# SHDN-S07-V00-PSU.net
KiCad netlist of a schematic drawn in Altium Designer
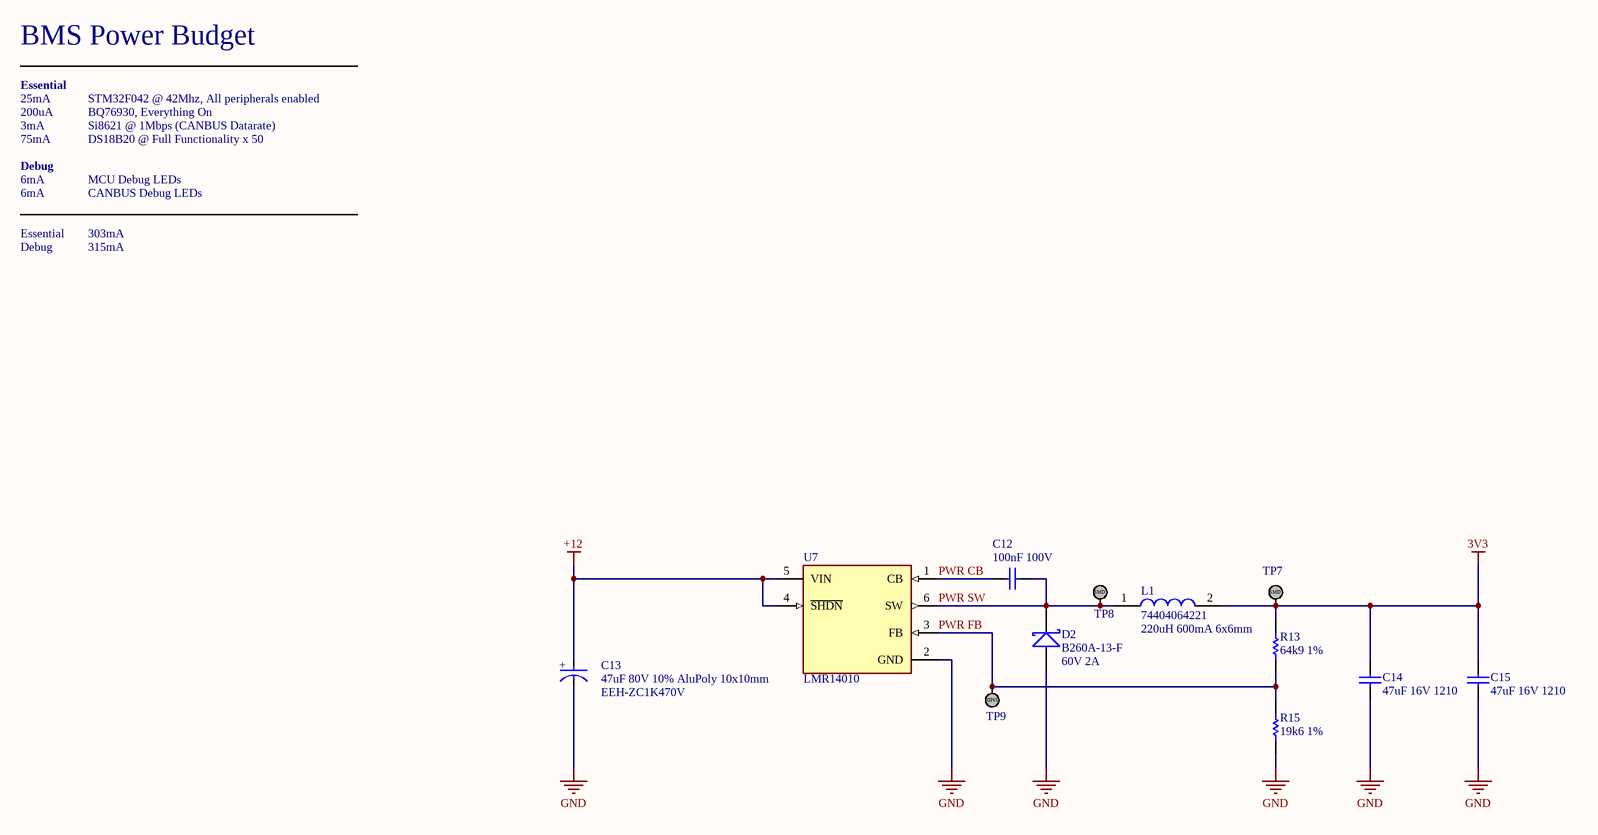
[diagram p0: SHDN-S07-V00-PSU.SchDoc]

(export (version "E")
  (design (tool "Eeschema 10.0.6"))
  (components
    (comp (ref "C12")
      (value "100nF 100V")
      (footprint "Cap_Ceramic_0603")
      (description "Capacitor, Ceramic, SMD, 100nF, 100V, 5%, X7R, 0603")
      (libsource (lib "StandardCapacitors") (part "100nF 100V 5% X7R 0603"))
    )
    (comp (ref "C13")
      (value "47uF 80V 10% AluPoly 10x10mm")
      (footprint "CAP_ALU_10x10mm")
      (description "Capacitor, AluPoly, SMD, 47uF, 80V, 10%, AluPoly, 10x10mm")
      (libsource (lib "StandardCapacitors") (part "47uF 80V 10% AluPoly 10x10mm"))
    )
    (comp (ref "C14")
      (value "47uF 16V 1210")
      (footprint "Cap_Ceramic_0603")
      (description "Capacitor, Ceramic, SMD, 47uF, 16V, 5%, X7R, 1210")
      (libsource (lib "StandardCapacitors") (part "47uF 16V 10% X7R 1210"))
    )
    (comp (ref "C15")
      (value "47uF 16V 1210")
      (footprint "Cap_Ceramic_0603")
      (description "Capacitor, Ceramic, SMD, 47uF, 16V, 5%, X7R, 1210")
      (libsource (lib "StandardCapacitors") (part "47uF 16V 10% X7R 1210"))
    )
    (comp (ref "D2")
      (value "B260A-13-F")
      (footprint "SMA")
      (description "Diode, Schottky Barrier Rectifier, 60 V, 2 A, B260A-13-F")
      (libsource (lib "QUTMS_DiodeLibrary") (part "B260A-13-F"))
    )
    (comp (ref "L1")
      (value "74404064221")
      (footprint "Inductor_6x6mm")
      (description "FIXED IND 220UH 660MA 850 MOHM")
      (libsource (lib "QUTMS_InductorLibrary") (part "74404064221"))
    )
    (comp (ref "R13")
      (value "64k9 1%")
      (footprint "Res_ThinFilm_0603")
      (description "Resistor, SMD, 64k9, 0.1W, 5%, 0603")
      (libsource (lib "StandardResistors") (part "64k9 1% 0603"))
    )
    (comp (ref "R15")
      (value "19k6 1%")
      (footprint "Res_ThinFilm_0603")
      (description "Resistor, SMD, 19k6, 0.1W, 5%, 0603")
      (libsource (lib "StandardResistors") (part "19k6 1% 0603"))
    )
    (comp (ref "TP7")
      (value "TestPoint_SMD")
      (footprint "TestPointSMD")
      (libsource (lib "StandardTest") (part "TestPoint_SMD"))
    )
    (comp (ref "TP8")
      (value "TestPoint_SMD")
      (footprint "TestPointSMD")
      (libsource (lib "StandardTest") (part "TestPoint_SMD"))
    )
    (comp (ref "TP9")
      (value "TestPoint_SMD")
      (footprint "TestPointSMD")
      (libsource (lib "StandardTest") (part "TestPoint_SMD"))
    )
    (comp (ref "U7")
      (value "LMR14010")
      (footprint "LMR14010")
      (libsource (lib "QUTMS_PowerSupplyLibrary") (part "LMR14010"))
    )
  )
  (nets
    (net (code "1") (name "+12") (class "Default")
      (node (ref "C13") (pin "A") (pinfunction "A_A") (pintype "passive"))
      (node (ref "U7") (pin "4") (pinfunction "~{SHDN}_4") (pintype "input"))
      (node (ref "U7") (pin "5") (pinfunction "VIN_5") (pintype "power_in"))
    )
    (net (code "2") (name "/PWR CB") (class "Default")
      (node (ref "C12") (pin "1") (pinfunction "1_1") (pintype "passive"))
      (node (ref "U7") (pin "1") (pinfunction "CB_1") (pintype "input"))
    )
    (net (code "3") (name "/PWR FB") (class "Default")
      (node (ref "R13") (pin "1") (pinfunction "1_1") (pintype "passive"))
      (node (ref "R15") (pin "2") (pinfunction "2_2") (pintype "passive"))
      (node (ref "TP9") (pin "1") (pinfunction "1_1") (pintype "passive"))
      (node (ref "U7") (pin "3") (pinfunction "FB_3") (pintype "input"))
    )
    (net (code "4") (name "/PWR SW") (class "Default")
      (node (ref "C12") (pin "2") (pinfunction "2_2") (pintype "passive"))
      (node (ref "D2") (pin "2") (pinfunction "K_2") (pintype "passive"))
      (node (ref "L1") (pin "1") (pinfunction "1_1") (pintype "passive"))
      (node (ref "TP8") (pin "1") (pinfunction "1_1") (pintype "passive"))
      (node (ref "U7") (pin "6") (pinfunction "SW_6") (pintype "output"))
    )
    (net (code "5") (name "3V3") (class "Default")
      (node (ref "C14") (pin "2") (pinfunction "2_2") (pintype "passive"))
      (node (ref "C15") (pin "2") (pinfunction "2_2") (pintype "passive"))
      (node (ref "L1") (pin "2") (pinfunction "2_2") (pintype "passive"))
      (node (ref "R13") (pin "2") (pinfunction "2_2") (pintype "passive"))
      (node (ref "TP7") (pin "1") (pinfunction "1_1") (pintype "passive"))
    )
    (net (code "6") (name "GND") (class "Default")
      (node (ref "C13") (pin "K") (pinfunction "K_K") (pintype "passive"))
      (node (ref "C14") (pin "1") (pinfunction "1_1") (pintype "passive"))
      (node (ref "C15") (pin "1") (pinfunction "1_1") (pintype "passive"))
      (node (ref "D2") (pin "1") (pinfunction "A_1") (pintype "passive"))
      (node (ref "R15") (pin "1") (pinfunction "1_1") (pintype "passive"))
      (node (ref "U7") (pin "2") (pinfunction "GND_2") (pintype "power_in"))
    )
  )
)
